# MCU_L4.net
KiCad netlist of a schematic drawn in Altium Designer
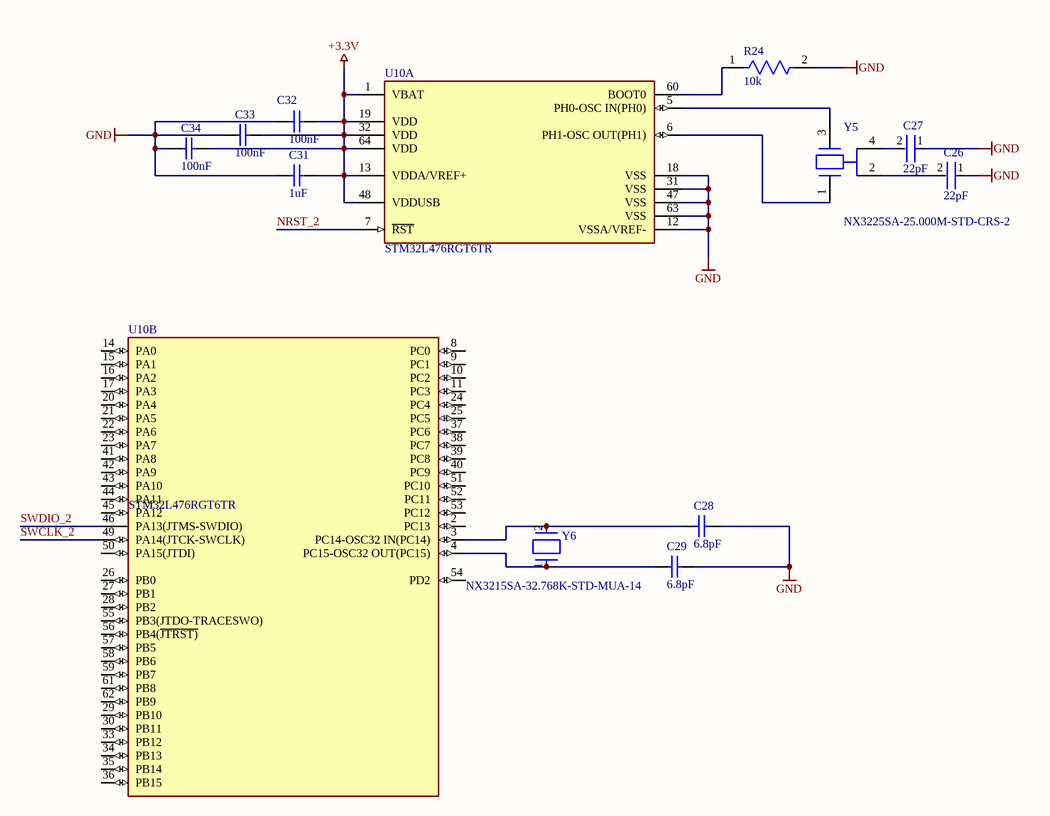
[diagram p0: MCU_L4.SchDoc]

(export (version "E")
  (design (tool "Eeschema 10.0.6"))
  (components
    (comp (ref "C26")
      (value "22pF")
      (footprint "FP-C0805C-DN-MFG")
      (description "CAP CER 22PF 100V 10% NP0 0805")
      (fields
        (field (name "MANUFACTURER PART NUMBER") "C0805C220K1GACTU")
        (field (name "OCTOPART") "https://octopart.com/c0805c220k1gactu-kemet-9138624")
      )
      (libsource (lib "Altium Content Vault") (part "b4654b650e69147ec39a6b967a45e02"))
    )
    (comp (ref "C27")
      (value "22pF")
      (footprint "FP-C0805C-DN-MFG")
      (description "CAP CER 22PF 100V 10% NP0 0805")
      (fields
        (field (name "MANUFACTURER PART NUMBER") "C0805C220K1GACTU")
        (field (name "OCTOPART") "https://octopart.com/c0805c220k1gactu-kemet-9138624")
      )
      (libsource (lib "Altium Content Vault") (part "b4654b650e69147ec39a6b967a45e02"))
    )
    (comp (ref "C28")
      (value "6.8pF")
      (footprint "CAPC2013X94X50NL20T25")
      (fields
        (field (name "PART NUMBER") "08051A6R8DAT2A")
        (field (name "MANUFACTURER") "AVX Interconnect / Elco")
      )
      (libsource (lib "Altium Content Vault") (part "CAP"))
    )
    (comp (ref "C29")
      (value "6.8pF")
      (footprint "CAPC2013X94X50NL20T25")
      (fields
        (field (name "PART NUMBER") "08051A6R8DAT2A")
        (field (name "MANUFACTURER") "AVX Interconnect / Elco")
      )
      (libsource (lib "Altium Content Vault") (part "CAP"))
    )
    (comp (ref "C31")
      (value "1uF")
      (footprint "CAPC2013X145X50NL20T20")
      (fields (field (name "PART NUMBER") "VJ0805Y105KXQRW1BC") (field (name "MANUFACTURER") "Vitramon"))
      (libsource (lib "Altium Content Vault") (part "CAP"))
    )
    (comp (ref "C32")
      (value "100nF")
      (footprint "CAPC2013X140X50ML20T25")
      (fields
        (field (name "PART NUMBER") "0805DD104KAT2A")
        (field (name "MANUFACTURER") "AVX Interconnect / Elco")
      )
      (libsource (lib "Altium Content Vault") (part "CAP"))
    )
    (comp (ref "C33")
      (value "100nF")
      (footprint "CAPC2013X140X50ML20T25")
      (fields
        (field (name "PART NUMBER") "0805DD104KAT2A")
        (field (name "MANUFACTURER") "AVX Interconnect / Elco")
      )
      (libsource (lib "Altium Content Vault") (part "CAP"))
    )
    (comp (ref "C34")
      (value "100nF")
      (footprint "CAPC2013X140X50ML20T25")
      (fields
        (field (name "PART NUMBER") "0805DD104KAT2A")
        (field (name "MANUFACTURER") "AVX Interconnect / Elco")
      )
      (libsource (lib "Altium Content Vault") (part "CAP"))
    )
    (comp (ref "R24")
      (value "10k")
      (footprint "FP-CRGP0805-IPC_C")
      (description "CRGP 0805 10K 1%")
      (fields (field (name "MANUFACTURER PART NUMBER") "CRGP0805F10K") (field (name "MANUFACTURER") "TE"))
      (libsource (lib "Altium Content Vault") (part "1029c3af85768c4190bb7ad29bc67b5"))
    )
    (comp (ref "U10")
      (value "STM32L476RGT6TR")
      (footprint "FP-LQFP64-5W-MFG")
      (description "IC MCU 32BIT 1MB FLASH 64LQFP")
      (fields
        (field (name "OCTOPART") "https://octopart.com/stm32l476rgt6tr-stmicroelectronics-74146120")
        (field (name "MANUFACTURER") "STMicroelectronics")
      )
      (libsource (lib "Altium Content Vault") (part "87b63bd17e71f2d821570a63d08c5bc"))
    )
    (comp (ref "Y5")
      (value "NX3225SA-25.000M-STD-CRS-2")
      (footprint "FP-NX3225SA-MFG")
      (description "CRYSTAL 25.0000MHZ 8PF SMD")
      (fields
        (field (name "OCTOPART") "https://octopart.com/nx3225sa-25.000m-std-crs-2-ndk-51374293")
        (field (name "MANUFACTURER") "NDK")
      )
      (libsource (lib "Altium Content Vault") (part "2e6e5a9c86ccbddb5e6335a7c0ff6ff"))
    )
    (comp (ref "Y6")
      (value "NX3215SA-32.768K-STD-MUA-14")
      (footprint "FP-NX3215SA-MFG")
      (description "NX3215SA-32.768K-STD-MUA-14 Parallel - Fundamental Quartz Crystal, 0.032768MHz Nom")
      (libsource (lib "Altium Content Vault") (part "c23a69dc6c9e2f18f2079038eb95dd1"))
    )
  )
  (nets
    (net (code "1") (name "+3.3V") (class "Default")
      (node (ref "C31") (pin "1") (pinfunction "1_1") (pintype "passive"))
      (node (ref "C32") (pin "2") (pinfunction "2_2") (pintype "passive"))
      (node (ref "C33") (pin "2") (pinfunction "2_2") (pintype "passive"))
      (node (ref "C34") (pin "2") (pinfunction "2_2") (pintype "passive"))
      (node (ref "U10") (pin "1") (pinfunction "VBAT_1") (pintype "power_in"))
      (node (ref "U10") (pin "13") (pinfunction "VDDA/VREF+_13") (pintype "power_in"))
      (node (ref "U10") (pin "19") (pinfunction "VDD_19") (pintype "power_in"))
      (node (ref "U10") (pin "32") (pinfunction "VDD_32") (pintype "power_in"))
      (node (ref "U10") (pin "48") (pinfunction "VDDUSB_48") (pintype "power_in"))
      (node (ref "U10") (pin "64") (pinfunction "VDD_64") (pintype "power_in"))
    )
    (net (code "2") (name "/NRST_2") (class "Default")
      (node (ref "U10") (pin "7") (pinfunction "~{RST}_7") (pintype "input"))
    )
    (net (code "3") (name "/SWCLK_2") (class "Default")
      (node (ref "U10") (pin "49") (pinfunction "PA14(JTCK-SWCLK)_49") (pintype "bidirectional"))
    )
    (net (code "4") (name "/SWDIO_2") (class "Default")
      (node (ref "U10") (pin "46") (pinfunction "PA13(JTMS-SWDIO)_46") (pintype "power_in"))
    )
    (net (code "5") (name "GND") (class "Default")
      (node (ref "C26") (pin "1") (pinfunction "1_1") (pintype "passive"))
      (node (ref "C27") (pin "1") (pinfunction "1_1") (pintype "passive"))
      (node (ref "C28") (pin "1") (pinfunction "1_1") (pintype "passive"))
      (node (ref "C29") (pin "2") (pinfunction "2_2") (pintype "passive"))
      (node (ref "C31") (pin "2") (pinfunction "2_2") (pintype "passive"))
      (node (ref "C32") (pin "1") (pinfunction "1_1") (pintype "passive"))
      (node (ref "C33") (pin "1") (pinfunction "1_1") (pintype "passive"))
      (node (ref "C34") (pin "1") (pinfunction "1_1") (pintype "passive"))
      (node (ref "R24") (pin "2") (pinfunction "2_2") (pintype "passive"))
      (node (ref "U10") (pin "12") (pinfunction "VSSA/VREF-_12") (pintype "power_in"))
      (node (ref "U10") (pin "18") (pinfunction "VSS_18") (pintype "power_in"))
      (node (ref "U10") (pin "31") (pinfunction "VSS_31") (pintype "power_in"))
      (node (ref "U10") (pin "47") (pinfunction "VSS_47") (pintype "power_in"))
      (node (ref "U10") (pin "63") (pinfunction "VSS_63") (pintype "power_in"))
    )
    (net (code "6") (name "Net-(C26-Pad2)") (class "Default")
      (node (ref "C26") (pin "2") (pinfunction "2_2") (pintype "passive"))
      (node (ref "Y5") (pin "2") (pinfunction "GND_2") (pintype "power_in"))
    )
    (net (code "7") (name "Net-(C27-Pad2)") (class "Default")
      (node (ref "C27") (pin "2") (pinfunction "2_2") (pintype "passive"))
      (node (ref "Y5") (pin "4") (pinfunction "GND_4") (pintype "power_in"))
    )
    (net (code "8") (name "Net-(U10A-BOOT0)") (class "Default")
      (node (ref "R24") (pin "1") (pinfunction "1_1") (pintype "passive"))
      (node (ref "U10") (pin "60") (pinfunction "BOOT0_60") (pintype "passive"))
    )
    (net (code "9") (name "Net-(U10A-PH0-OSC_IN(PH0))") (class "Default")
      (node (ref "U10") (pin "5") (pinfunction "PH0-OSC_IN(PH0)_5") (pintype "bidirectional"))
      (node (ref "Y5") (pin "3") (pinfunction "3_3") (pintype "passive"))
    )
    (net (code "10") (name "Net-(U10A-PH1-OSC_OUT(PH1))") (class "Default")
      (node (ref "U10") (pin "6") (pinfunction "PH1-OSC_OUT(PH1)_6") (pintype "bidirectional"))
      (node (ref "Y5") (pin "1") (pinfunction "1_1") (pintype "passive"))
    )
    (net (code "11") (name "Net-(U10B-PC14-OSC32_IN(PC14))") (class "Default")
      (node (ref "C28") (pin "2") (pinfunction "2_2") (pintype "passive"))
      (node (ref "U10") (pin "3") (pinfunction "PC14-OSC32_IN(PC14)_3") (pintype "bidirectional"))
      (node (ref "Y6") (pin "2") (pinfunction "2_2") (pintype "passive"))
    )
    (net (code "12") (name "Net-(U10B-PC15-OSC32_OUT(PC15))") (class "Default")
      (node (ref "C29") (pin "1") (pinfunction "1_1") (pintype "passive"))
      (node (ref "U10") (pin "4") (pinfunction "PC15-OSC32_OUT(PC15)_4") (pintype "bidirectional"))
      (node (ref "Y6") (pin "1") (pinfunction "1_1") (pintype "passive"))
    )
    (net (code "13") (name "unconnected-(U10B-PA0-Pad14)") (class "Default")
      (node (ref "U10") (pin "14") (pinfunction "PA0_14") (pintype "bidirectional"))
    )
    (net (code "14") (name "unconnected-(U10B-PA1-Pad15)") (class "Default")
      (node (ref "U10") (pin "15") (pinfunction "PA1_15") (pintype "bidirectional"))
    )
    (net (code "15") (name "unconnected-(U10B-PA2-Pad16)") (class "Default")
      (node (ref "U10") (pin "16") (pinfunction "PA2_16") (pintype "bidirectional"))
    )
    (net (code "16") (name "unconnected-(U10B-PA3-Pad17)") (class "Default")
      (node (ref "U10") (pin "17") (pinfunction "PA3_17") (pintype "bidirectional"))
    )
    (net (code "17") (name "unconnected-(U10B-PA4-Pad20)") (class "Default")
      (node (ref "U10") (pin "20") (pinfunction "PA4_20") (pintype "bidirectional"))
    )
    (net (code "18") (name "unconnected-(U10B-PA5-Pad21)") (class "Default")
      (node (ref "U10") (pin "21") (pinfunction "PA5_21") (pintype "bidirectional"))
    )
    (net (code "19") (name "unconnected-(U10B-PA6-Pad22)") (class "Default")
      (node (ref "U10") (pin "22") (pinfunction "PA6_22") (pintype "bidirectional"))
    )
    (net (code "20") (name "unconnected-(U10B-PA7-Pad23)") (class "Default")
      (node (ref "U10") (pin "23") (pinfunction "PA7_23") (pintype "bidirectional"))
    )
    (net (code "21") (name "unconnected-(U10B-PA8-Pad41)") (class "Default")
      (node (ref "U10") (pin "41") (pinfunction "PA8_41") (pintype "bidirectional"))
    )
    (net (code "22") (name "unconnected-(U10B-PA9-Pad42)") (class "Default")
      (node (ref "U10") (pin "42") (pinfunction "PA9_42") (pintype "bidirectional"))
    )
    (net (code "23") (name "unconnected-(U10B-PA10-Pad43)") (class "Default")
      (node (ref "U10") (pin "43") (pinfunction "PA10_43") (pintype "bidirectional"))
    )
    (net (code "24") (name "unconnected-(U10B-PA11-Pad44)") (class "Default")
      (node (ref "U10") (pin "44") (pinfunction "PA11_44") (pintype "bidirectional"))
    )
    (net (code "25") (name "unconnected-(U10B-PA12-Pad45)") (class "Default")
      (node (ref "U10") (pin "45") (pinfunction "PA12_45") (pintype "bidirectional"))
    )
    (net (code "26") (name "unconnected-(U10B-PA15(JTDI)-Pad50)") (class "Default")
      (node (ref "U10") (pin "50") (pinfunction "PA15(JTDI)_50") (pintype "bidirectional"))
    )
    (net (code "27") (name "unconnected-(U10B-PB0-Pad26)") (class "Default")
      (node (ref "U10") (pin "26") (pinfunction "PB0_26") (pintype "bidirectional"))
    )
    (net (code "28") (name "unconnected-(U10B-PB1-Pad27)") (class "Default")
      (node (ref "U10") (pin "27") (pinfunction "PB1_27") (pintype "bidirectional"))
    )
    (net (code "29") (name "unconnected-(U10B-PB2-Pad28)") (class "Default")
      (node (ref "U10") (pin "28") (pinfunction "PB2_28") (pintype "bidirectional"))
    )
    (net (code "30") (name "unconnected-(U10B-PB3(JTDO-TRACESWO)-Pad55)") (class "Default")
      (node (ref "U10") (pin "55") (pinfunction "PB3(JTDO-TRACESWO)_55") (pintype "bidirectional"))
    )
    (net (code "31") (name "unconnected-(U10B-PB4(~{JTRST)}-Pad56)") (class "Default")
      (node (ref "U10") (pin "56") (pinfunction "PB4(~{JTRST)}_56") (pintype "bidirectional"))
    )
    (net (code "32") (name "unconnected-(U10B-PB5-Pad57)") (class "Default")
      (node (ref "U10") (pin "57") (pinfunction "PB5_57") (pintype "bidirectional"))
    )
    (net (code "33") (name "unconnected-(U10B-PB6-Pad58)") (class "Default")
      (node (ref "U10") (pin "58") (pinfunction "PB6_58") (pintype "bidirectional"))
    )
    (net (code "34") (name "unconnected-(U10B-PB7-Pad59)") (class "Default")
      (node (ref "U10") (pin "59") (pinfunction "PB7_59") (pintype "bidirectional"))
    )
    (net (code "35") (name "unconnected-(U10B-PB8-Pad61)") (class "Default")
      (node (ref "U10") (pin "61") (pinfunction "PB8_61") (pintype "bidirectional"))
    )
    (net (code "36") (name "unconnected-(U10B-PB9-Pad62)") (class "Default")
      (node (ref "U10") (pin "62") (pinfunction "PB9_62") (pintype "bidirectional"))
    )
    (net (code "37") (name "unconnected-(U10B-PB10-Pad29)") (class "Default")
      (node (ref "U10") (pin "29") (pinfunction "PB10_29") (pintype "bidirectional"))
    )
    (net (code "38") (name "unconnected-(U10B-PB11-Pad30)") (class "Default")
      (node (ref "U10") (pin "30") (pinfunction "PB11_30") (pintype "bidirectional"))
    )
    (net (code "39") (name "unconnected-(U10B-PB12-Pad33)") (class "Default")
      (node (ref "U10") (pin "33") (pinfunction "PB12_33") (pintype "bidirectional"))
    )
    (net (code "40") (name "unconnected-(U10B-PB13-Pad34)") (class "Default")
      (node (ref "U10") (pin "34") (pinfunction "PB13_34") (pintype "bidirectional"))
    )
    (net (code "41") (name "unconnected-(U10B-PB14-Pad35)") (class "Default")
      (node (ref "U10") (pin "35") (pinfunction "PB14_35") (pintype "bidirectional"))
    )
    (net (code "42") (name "unconnected-(U10B-PB15-Pad36)") (class "Default")
      (node (ref "U10") (pin "36") (pinfunction "PB15_36") (pintype "bidirectional"))
    )
    (net (code "43") (name "unconnected-(U10B-PC0-Pad8)") (class "Default")
      (node (ref "U10") (pin "8") (pinfunction "PC0_8") (pintype "bidirectional"))
    )
    (net (code "44") (name "unconnected-(U10B-PC1-Pad9)") (class "Default")
      (node (ref "U10") (pin "9") (pinfunction "PC1_9") (pintype "bidirectional"))
    )
    (net (code "45") (name "unconnected-(U10B-PC2-Pad10)") (class "Default")
      (node (ref "U10") (pin "10") (pinfunction "PC2_10") (pintype "bidirectional"))
    )
    (net (code "46") (name "unconnected-(U10B-PC3-Pad11)") (class "Default")
      (node (ref "U10") (pin "11") (pinfunction "PC3_11") (pintype "bidirectional"))
    )
    (net (code "47") (name "unconnected-(U10B-PC4-Pad24)") (class "Default")
      (node (ref "U10") (pin "24") (pinfunction "PC4_24") (pintype "bidirectional"))
    )
    (net (code "48") (name "unconnected-(U10B-PC5-Pad25)") (class "Default")
      (node (ref "U10") (pin "25") (pinfunction "PC5_25") (pintype "bidirectional"))
    )
    (net (code "49") (name "unconnected-(U10B-PC6-Pad37)") (class "Default")
      (node (ref "U10") (pin "37") (pinfunction "PC6_37") (pintype "bidirectional"))
    )
    (net (code "50") (name "unconnected-(U10B-PC7-Pad38)") (class "Default")
      (node (ref "U10") (pin "38") (pinfunction "PC7_38") (pintype "bidirectional"))
    )
    (net (code "51") (name "unconnected-(U10B-PC8-Pad39)") (class "Default")
      (node (ref "U10") (pin "39") (pinfunction "PC8_39") (pintype "bidirectional"))
    )
    (net (code "52") (name "unconnected-(U10B-PC9-Pad40)") (class "Default")
      (node (ref "U10") (pin "40") (pinfunction "PC9_40") (pintype "bidirectional"))
    )
    (net (code "53") (name "unconnected-(U10B-PC10-Pad51)") (class "Default")
      (node (ref "U10") (pin "51") (pinfunction "PC10_51") (pintype "bidirectional"))
    )
    (net (code "54") (name "unconnected-(U10B-PC11-Pad52)") (class "Default")
      (node (ref "U10") (pin "52") (pinfunction "PC11_52") (pintype "bidirectional"))
    )
    (net (code "55") (name "unconnected-(U10B-PC12-Pad53)") (class "Default")
      (node (ref "U10") (pin "53") (pinfunction "PC12_53") (pintype "bidirectional"))
    )
    (net (code "56") (name "unconnected-(U10B-PC13-Pad2)") (class "Default")
      (node (ref "U10") (pin "2") (pinfunction "PC13_2") (pintype "bidirectional"))
    )
    (net (code "57") (name "unconnected-(U10B-PD2-Pad54)") (class "Default")
      (node (ref "U10") (pin "54") (pinfunction "PD2_54") (pintype "bidirectional"))
    )
  )
)
